# Peripheral.net
KiCad netlist of a schematic drawn in Altium Designer
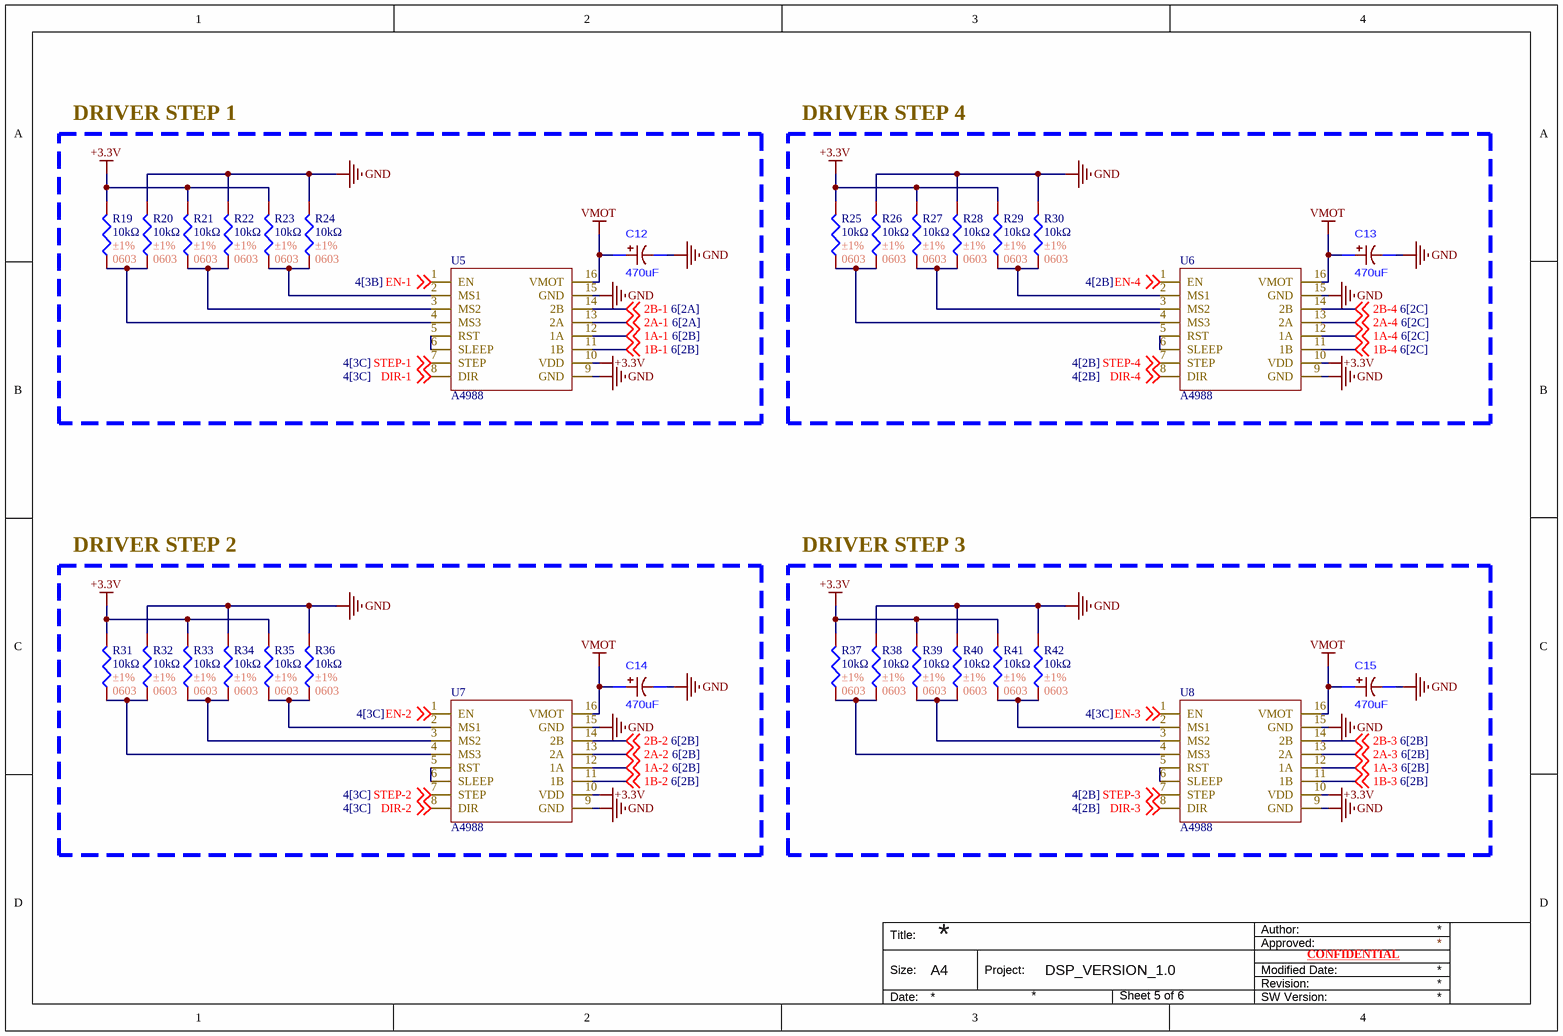
[diagram p0: Peripheral.SchDoc]

(export (version "E")
  (design (tool "Eeschema 10.0.6"))
  (components
    (comp (ref "C12")
      (value "470uF")
      (footprint "470uF 35V, D10xL13mm")
      (description "470uF ±20% 35V Through Hole,D10xL13mm")
      (fields (field (name "MANUFACTURER") "AISHI") (field (name "MFR. PART #") "SPZ1VM471G13O00RAXXX"))
      (libsource (lib "Capital") (part "470uF  35V, D10xL13mm"))
    )
    (comp (ref "C13")
      (value "470uF")
      (footprint "470uF 35V, D10xL13mm")
      (description "470uF ±20% 35V Through Hole,D10xL13mm")
      (fields (field (name "MANUFACTURER") "AISHI") (field (name "MFR. PART #") "SPZ1VM471G13O00RAXXX"))
      (libsource (lib "Capital") (part "470uF  35V, D10xL13mm"))
    )
    (comp (ref "C14")
      (value "470uF")
      (footprint "470uF 35V, D10xL13mm")
      (description "470uF ±20% 35V Through Hole,D10xL13mm")
      (fields (field (name "MANUFACTURER") "AISHI") (field (name "MFR. PART #") "SPZ1VM471G13O00RAXXX"))
      (libsource (lib "Capital") (part "470uF  35V, D10xL13mm"))
    )
    (comp (ref "C15")
      (value "470uF")
      (footprint "470uF 35V, D10xL13mm")
      (description "470uF ±20% 35V Through Hole,D10xL13mm")
      (fields (field (name "MANUFACTURER") "AISHI") (field (name "MFR. PART #") "SPZ1VM471G13O00RAXXX"))
      (libsource (lib "Capital") (part "470uF  35V, D10xL13mm"))
    )
    (comp (ref "R19")
      (value "10kΩ")
      (footprint "R0603")
      (description "62.5mW Thick Film Resistor 50V ±1% ±200ppm/℃ 10Ω 0402 Chip Resistor - Surface Mount ROHS")
      (fields
        (field (name "MANUFACTURER") "YAGEO")
        (field (name "MFR. PART #") "RC0402FR-0710RL")
        (field (name "TOLERANCE") "±1%")
        (field (name "PACKAGE") "0603")
      )
      (libsource (lib "Resistor") (part "R0603_10kΩ_±1%"))
    )
    (comp (ref "R20")
      (value "10kΩ")
      (footprint "R0603")
      (description "62.5mW Thick Film Resistor 50V ±1% ±200ppm/℃ 10Ω 0402 Chip Resistor - Surface Mount ROHS")
      (fields
        (field (name "MANUFACTURER") "YAGEO")
        (field (name "MFR. PART #") "RC0402FR-0710RL")
        (field (name "TOLERANCE") "±1%")
        (field (name "PACKAGE") "0603")
      )
      (libsource (lib "Resistor") (part "R0603_10kΩ_±1%"))
    )
    (comp (ref "R21")
      (value "10kΩ")
      (footprint "R0603")
      (description "62.5mW Thick Film Resistor 50V ±1% ±200ppm/℃ 10Ω 0402 Chip Resistor - Surface Mount ROHS")
      (fields
        (field (name "MANUFACTURER") "YAGEO")
        (field (name "MFR. PART #") "RC0402FR-0710RL")
        (field (name "TOLERANCE") "±1%")
        (field (name "PACKAGE") "0603")
      )
      (libsource (lib "Resistor") (part "R0603_10kΩ_±1%"))
    )
    (comp (ref "R22")
      (value "10kΩ")
      (footprint "R0603")
      (description "62.5mW Thick Film Resistor 50V ±1% ±200ppm/℃ 10Ω 0402 Chip Resistor - Surface Mount ROHS")
      (fields
        (field (name "MANUFACTURER") "YAGEO")
        (field (name "MFR. PART #") "RC0402FR-0710RL")
        (field (name "TOLERANCE") "±1%")
        (field (name "PACKAGE") "0603")
      )
      (libsource (lib "Resistor") (part "R0603_10kΩ_±1%"))
    )
    (comp (ref "R23")
      (value "10kΩ")
      (footprint "R0603")
      (description "62.5mW Thick Film Resistor 50V ±1% ±200ppm/℃ 10Ω 0402 Chip Resistor - Surface Mount ROHS")
      (fields
        (field (name "MANUFACTURER") "YAGEO")
        (field (name "MFR. PART #") "RC0402FR-0710RL")
        (field (name "TOLERANCE") "±1%")
        (field (name "PACKAGE") "0603")
      )
      (libsource (lib "Resistor") (part "R0603_10kΩ_±1%"))
    )
    (comp (ref "R24")
      (value "10kΩ")
      (footprint "R0603")
      (description "62.5mW Thick Film Resistor 50V ±1% ±200ppm/℃ 10Ω 0402 Chip Resistor - Surface Mount ROHS")
      (fields
        (field (name "MANUFACTURER") "YAGEO")
        (field (name "MFR. PART #") "RC0402FR-0710RL")
        (field (name "TOLERANCE") "±1%")
        (field (name "PACKAGE") "0603")
      )
      (libsource (lib "Resistor") (part "R0603_10kΩ_±1%"))
    )
    (comp (ref "R25")
      (value "10kΩ")
      (footprint "R0603")
      (description "62.5mW Thick Film Resistor 50V ±1% ±200ppm/℃ 10Ω 0402 Chip Resistor - Surface Mount ROHS")
      (fields
        (field (name "MANUFACTURER") "YAGEO")
        (field (name "MFR. PART #") "RC0402FR-0710RL")
        (field (name "TOLERANCE") "±1%")
        (field (name "PACKAGE") "0603")
      )
      (libsource (lib "Resistor") (part "R0603_10kΩ_±1%"))
    )
    (comp (ref "R26")
      (value "10kΩ")
      (footprint "R0603")
      (description "62.5mW Thick Film Resistor 50V ±1% ±200ppm/℃ 10Ω 0402 Chip Resistor - Surface Mount ROHS")
      (fields
        (field (name "MANUFACTURER") "YAGEO")
        (field (name "MFR. PART #") "RC0402FR-0710RL")
        (field (name "TOLERANCE") "±1%")
        (field (name "PACKAGE") "0603")
      )
      (libsource (lib "Resistor") (part "R0603_10kΩ_±1%"))
    )
    (comp (ref "R27")
      (value "10kΩ")
      (footprint "R0603")
      (description "62.5mW Thick Film Resistor 50V ±1% ±200ppm/℃ 10Ω 0402 Chip Resistor - Surface Mount ROHS")
      (fields
        (field (name "MANUFACTURER") "YAGEO")
        (field (name "MFR. PART #") "RC0402FR-0710RL")
        (field (name "TOLERANCE") "±1%")
        (field (name "PACKAGE") "0603")
      )
      (libsource (lib "Resistor") (part "R0603_10kΩ_±1%"))
    )
    (comp (ref "R28")
      (value "10kΩ")
      (footprint "R0603")
      (description "62.5mW Thick Film Resistor 50V ±1% ±200ppm/℃ 10Ω 0402 Chip Resistor - Surface Mount ROHS")
      (fields
        (field (name "MANUFACTURER") "YAGEO")
        (field (name "MFR. PART #") "RC0402FR-0710RL")
        (field (name "TOLERANCE") "±1%")
        (field (name "PACKAGE") "0603")
      )
      (libsource (lib "Resistor") (part "R0603_10kΩ_±1%"))
    )
    (comp (ref "R29")
      (value "10kΩ")
      (footprint "R0603")
      (description "62.5mW Thick Film Resistor 50V ±1% ±200ppm/℃ 10Ω 0402 Chip Resistor - Surface Mount ROHS")
      (fields
        (field (name "MANUFACTURER") "YAGEO")
        (field (name "MFR. PART #") "RC0402FR-0710RL")
        (field (name "TOLERANCE") "±1%")
        (field (name "PACKAGE") "0603")
      )
      (libsource (lib "Resistor") (part "R0603_10kΩ_±1%"))
    )
    (comp (ref "R30")
      (value "10kΩ")
      (footprint "R0603")
      (description "62.5mW Thick Film Resistor 50V ±1% ±200ppm/℃ 10Ω 0402 Chip Resistor - Surface Mount ROHS")
      (fields
        (field (name "MANUFACTURER") "YAGEO")
        (field (name "MFR. PART #") "RC0402FR-0710RL")
        (field (name "TOLERANCE") "±1%")
        (field (name "PACKAGE") "0603")
      )
      (libsource (lib "Resistor") (part "R0603_10kΩ_±1%"))
    )
    (comp (ref "R31")
      (value "10kΩ")
      (footprint "R0603")
      (description "62.5mW Thick Film Resistor 50V ±1% ±200ppm/℃ 10Ω 0402 Chip Resistor - Surface Mount ROHS")
      (fields
        (field (name "MANUFACTURER") "YAGEO")
        (field (name "MFR. PART #") "RC0402FR-0710RL")
        (field (name "TOLERANCE") "±1%")
        (field (name "PACKAGE") "0603")
      )
      (libsource (lib "Resistor") (part "R0603_10kΩ_±1%"))
    )
    (comp (ref "R32")
      (value "10kΩ")
      (footprint "R0603")
      (description "62.5mW Thick Film Resistor 50V ±1% ±200ppm/℃ 10Ω 0402 Chip Resistor - Surface Mount ROHS")
      (fields
        (field (name "MANUFACTURER") "YAGEO")
        (field (name "MFR. PART #") "RC0402FR-0710RL")
        (field (name "TOLERANCE") "±1%")
        (field (name "PACKAGE") "0603")
      )
      (libsource (lib "Resistor") (part "R0603_10kΩ_±1%"))
    )
    (comp (ref "R33")
      (value "10kΩ")
      (footprint "R0603")
      (description "62.5mW Thick Film Resistor 50V ±1% ±200ppm/℃ 10Ω 0402 Chip Resistor - Surface Mount ROHS")
      (fields
        (field (name "MANUFACTURER") "YAGEO")
        (field (name "MFR. PART #") "RC0402FR-0710RL")
        (field (name "TOLERANCE") "±1%")
        (field (name "PACKAGE") "0603")
      )
      (libsource (lib "Resistor") (part "R0603_10kΩ_±1%"))
    )
    (comp (ref "R34")
      (value "10kΩ")
      (footprint "R0603")
      (description "62.5mW Thick Film Resistor 50V ±1% ±200ppm/℃ 10Ω 0402 Chip Resistor - Surface Mount ROHS")
      (fields
        (field (name "MANUFACTURER") "YAGEO")
        (field (name "MFR. PART #") "RC0402FR-0710RL")
        (field (name "TOLERANCE") "±1%")
        (field (name "PACKAGE") "0603")
      )
      (libsource (lib "Resistor") (part "R0603_10kΩ_±1%"))
    )
    (comp (ref "R35")
      (value "10kΩ")
      (footprint "R0603")
      (description "62.5mW Thick Film Resistor 50V ±1% ±200ppm/℃ 10Ω 0402 Chip Resistor - Surface Mount ROHS")
      (fields
        (field (name "MANUFACTURER") "YAGEO")
        (field (name "MFR. PART #") "RC0402FR-0710RL")
        (field (name "TOLERANCE") "±1%")
        (field (name "PACKAGE") "0603")
      )
      (libsource (lib "Resistor") (part "R0603_10kΩ_±1%"))
    )
    (comp (ref "R36")
      (value "10kΩ")
      (footprint "R0603")
      (description "62.5mW Thick Film Resistor 50V ±1% ±200ppm/℃ 10Ω 0402 Chip Resistor - Surface Mount ROHS")
      (fields
        (field (name "MANUFACTURER") "YAGEO")
        (field (name "MFR. PART #") "RC0402FR-0710RL")
        (field (name "TOLERANCE") "±1%")
        (field (name "PACKAGE") "0603")
      )
      (libsource (lib "Resistor") (part "R0603_10kΩ_±1%"))
    )
    (comp (ref "R37")
      (value "10kΩ")
      (footprint "R0603")
      (description "62.5mW Thick Film Resistor 50V ±1% ±200ppm/℃ 10Ω 0402 Chip Resistor - Surface Mount ROHS")
      (fields
        (field (name "MANUFACTURER") "YAGEO")
        (field (name "MFR. PART #") "RC0402FR-0710RL")
        (field (name "TOLERANCE") "±1%")
        (field (name "PACKAGE") "0603")
      )
      (libsource (lib "Resistor") (part "R0603_10kΩ_±1%"))
    )
    (comp (ref "R38")
      (value "10kΩ")
      (footprint "R0603")
      (description "62.5mW Thick Film Resistor 50V ±1% ±200ppm/℃ 10Ω 0402 Chip Resistor - Surface Mount ROHS")
      (fields
        (field (name "MANUFACTURER") "YAGEO")
        (field (name "MFR. PART #") "RC0402FR-0710RL")
        (field (name "TOLERANCE") "±1%")
        (field (name "PACKAGE") "0603")
      )
      (libsource (lib "Resistor") (part "R0603_10kΩ_±1%"))
    )
    (comp (ref "R39")
      (value "10kΩ")
      (footprint "R0603")
      (description "62.5mW Thick Film Resistor 50V ±1% ±200ppm/℃ 10Ω 0402 Chip Resistor - Surface Mount ROHS")
      (fields
        (field (name "MANUFACTURER") "YAGEO")
        (field (name "MFR. PART #") "RC0402FR-0710RL")
        (field (name "TOLERANCE") "±1%")
        (field (name "PACKAGE") "0603")
      )
      (libsource (lib "Resistor") (part "R0603_10kΩ_±1%"))
    )
    (comp (ref "R40")
      (value "10kΩ")
      (footprint "R0603")
      (description "62.5mW Thick Film Resistor 50V ±1% ±200ppm/℃ 10Ω 0402 Chip Resistor - Surface Mount ROHS")
      (fields
        (field (name "MANUFACTURER") "YAGEO")
        (field (name "MFR. PART #") "RC0402FR-0710RL")
        (field (name "TOLERANCE") "±1%")
        (field (name "PACKAGE") "0603")
      )
      (libsource (lib "Resistor") (part "R0603_10kΩ_±1%"))
    )
    (comp (ref "R41")
      (value "10kΩ")
      (footprint "R0603")
      (description "62.5mW Thick Film Resistor 50V ±1% ±200ppm/℃ 10Ω 0402 Chip Resistor - Surface Mount ROHS")
      (fields
        (field (name "MANUFACTURER") "YAGEO")
        (field (name "MFR. PART #") "RC0402FR-0710RL")
        (field (name "TOLERANCE") "±1%")
        (field (name "PACKAGE") "0603")
      )
      (libsource (lib "Resistor") (part "R0603_10kΩ_±1%"))
    )
    (comp (ref "R42")
      (value "10kΩ")
      (footprint "R0603")
      (description "62.5mW Thick Film Resistor 50V ±1% ±200ppm/℃ 10Ω 0402 Chip Resistor - Surface Mount ROHS")
      (fields
        (field (name "MANUFACTURER") "YAGEO")
        (field (name "MFR. PART #") "RC0402FR-0710RL")
        (field (name "TOLERANCE") "±1%")
        (field (name "PACKAGE") "0603")
      )
      (libsource (lib "Resistor") (part "R0603_10kΩ_±1%"))
    )
    (comp (ref "U5")
      (value "A4988")
      (footprint "A4988-driver_step")
      (libsource (lib "IC") (part "Module_A4988"))
    )
    (comp (ref "U6")
      (value "A4988")
      (footprint "A4988-driver_step")
      (libsource (lib "IC") (part "Module_A4988"))
    )
    (comp (ref "U7")
      (value "A4988")
      (footprint "A4988-driver_step")
      (libsource (lib "IC") (part "Module_A4988"))
    )
    (comp (ref "U8")
      (value "A4988")
      (footprint "A4988-driver_step")
      (libsource (lib "IC") (part "Module_A4988"))
    )
  )
  (nets
    (net (code "1") (name "+3.3V") (class "Default")
      (node (ref "R19") (pin "2") (pinfunction "2_2") (pintype "passive"))
      (node (ref "R21") (pin "2") (pinfunction "2_2") (pintype "passive"))
      (node (ref "R23") (pin "2") (pinfunction "2_2") (pintype "passive"))
      (node (ref "R25") (pin "2") (pinfunction "2_2") (pintype "passive"))
      (node (ref "R27") (pin "2") (pinfunction "2_2") (pintype "passive"))
      (node (ref "R29") (pin "2") (pinfunction "2_2") (pintype "passive"))
      (node (ref "R31") (pin "2") (pinfunction "2_2") (pintype "passive"))
      (node (ref "R33") (pin "2") (pinfunction "2_2") (pintype "passive"))
      (node (ref "R35") (pin "2") (pinfunction "2_2") (pintype "passive"))
      (node (ref "R37") (pin "2") (pinfunction "2_2") (pintype "passive"))
      (node (ref "R39") (pin "2") (pinfunction "2_2") (pintype "passive"))
      (node (ref "R41") (pin "2") (pinfunction "2_2") (pintype "passive"))
      (node (ref "U5") (pin "10") (pinfunction "VDD_10") (pintype "passive"))
      (node (ref "U6") (pin "10") (pinfunction "VDD_10") (pintype "passive"))
      (node (ref "U7") (pin "10") (pinfunction "VDD_10") (pintype "passive"))
      (node (ref "U8") (pin "10") (pinfunction "VDD_10") (pintype "passive"))
    )
    (net (code "2") (name "1A-1") (class "Default")
      (node (ref "U5") (pin "12") (pinfunction "1A_12") (pintype "passive"))
    )
    (net (code "3") (name "1A-2") (class "Default")
      (node (ref "U7") (pin "12") (pinfunction "1A_12") (pintype "passive"))
    )
    (net (code "4") (name "1A-3") (class "Default")
      (node (ref "U8") (pin "12") (pinfunction "1A_12") (pintype "passive"))
    )
    (net (code "5") (name "1A-4") (class "Default")
      (node (ref "U6") (pin "12") (pinfunction "1A_12") (pintype "passive"))
    )
    (net (code "6") (name "1B-1") (class "Default")
      (node (ref "U5") (pin "11") (pinfunction "1B_11") (pintype "passive"))
    )
    (net (code "7") (name "1B-2") (class "Default")
      (node (ref "U7") (pin "11") (pinfunction "1B_11") (pintype "passive"))
    )
    (net (code "8") (name "1B-3") (class "Default")
      (node (ref "U8") (pin "11") (pinfunction "1B_11") (pintype "passive"))
    )
    (net (code "9") (name "1B-4") (class "Default")
      (node (ref "U6") (pin "11") (pinfunction "1B_11") (pintype "passive"))
    )
    (net (code "10") (name "2A-1") (class "Default")
      (node (ref "U5") (pin "13") (pinfunction "2A_13") (pintype "passive"))
    )
    (net (code "11") (name "2A-2") (class "Default")
      (node (ref "U7") (pin "13") (pinfunction "2A_13") (pintype "passive"))
    )
    (net (code "12") (name "2A-3") (class "Default")
      (node (ref "U8") (pin "13") (pinfunction "2A_13") (pintype "passive"))
    )
    (net (code "13") (name "2A-4") (class "Default")
      (node (ref "U6") (pin "13") (pinfunction "2A_13") (pintype "passive"))
    )
    (net (code "14") (name "2B-1") (class "Default")
      (node (ref "U5") (pin "14") (pinfunction "2B_14") (pintype "passive"))
    )
    (net (code "15") (name "2B-2") (class "Default")
      (node (ref "U7") (pin "14") (pinfunction "2B_14") (pintype "passive"))
    )
    (net (code "16") (name "2B-3") (class "Default")
      (node (ref "U8") (pin "14") (pinfunction "2B_14") (pintype "passive"))
    )
    (net (code "17") (name "2B-4") (class "Default")
      (node (ref "U6") (pin "14") (pinfunction "2B_14") (pintype "passive"))
    )
    (net (code "18") (name "DIR-1") (class "Default")
      (node (ref "U5") (pin "8") (pinfunction "DIR_8") (pintype "passive"))
    )
    (net (code "19") (name "DIR-2") (class "Default")
      (node (ref "U7") (pin "8") (pinfunction "DIR_8") (pintype "passive"))
    )
    (net (code "20") (name "DIR-3") (class "Default")
      (node (ref "U8") (pin "8") (pinfunction "DIR_8") (pintype "passive"))
    )
    (net (code "21") (name "DIR-4") (class "Default")
      (node (ref "U6") (pin "8") (pinfunction "DIR_8") (pintype "passive"))
    )
    (net (code "22") (name "EN-1") (class "Default")
      (node (ref "U5") (pin "1") (pinfunction "EN_1") (pintype "passive"))
    )
    (net (code "23") (name "EN-2") (class "Default")
      (node (ref "U7") (pin "1") (pinfunction "EN_1") (pintype "passive"))
    )
    (net (code "24") (name "EN-3") (class "Default")
      (node (ref "U8") (pin "1") (pinfunction "EN_1") (pintype "passive"))
    )
    (net (code "25") (name "EN-4") (class "Default")
      (node (ref "U6") (pin "1") (pinfunction "EN_1") (pintype "passive"))
    )
    (net (code "26") (name "GND") (class "Default")
      (node (ref "C12") (pin "2") (pinfunction "2_2") (pintype "passive"))
      (node (ref "C13") (pin "2") (pinfunction "2_2") (pintype "passive"))
      (node (ref "C14") (pin "2") (pinfunction "2_2") (pintype "passive"))
      (node (ref "C15") (pin "2") (pinfunction "2_2") (pintype "passive"))
      (node (ref "R20") (pin "2") (pinfunction "2_2") (pintype "passive"))
      (node (ref "R22") (pin "2") (pinfunction "2_2") (pintype "passive"))
      (node (ref "R24") (pin "2") (pinfunction "2_2") (pintype "passive"))
      (node (ref "R26") (pin "2") (pinfunction "2_2") (pintype "passive"))
      (node (ref "R28") (pin "2") (pinfunction "2_2") (pintype "passive"))
      (node (ref "R30") (pin "2") (pinfunction "2_2") (pintype "passive"))
      (node (ref "R32") (pin "2") (pinfunction "2_2") (pintype "passive"))
      (node (ref "R34") (pin "2") (pinfunction "2_2") (pintype "passive"))
      (node (ref "R36") (pin "2") (pinfunction "2_2") (pintype "passive"))
      (node (ref "R38") (pin "2") (pinfunction "2_2") (pintype "passive"))
      (node (ref "R40") (pin "2") (pinfunction "2_2") (pintype "passive"))
      (node (ref "R42") (pin "2") (pinfunction "2_2") (pintype "passive"))
      (node (ref "U5") (pin "15") (pinfunction "GND_15") (pintype "passive"))
      (node (ref "U5") (pin "9") (pinfunction "GND_9") (pintype "passive"))
      (node (ref "U6") (pin "15") (pinfunction "GND_15") (pintype "passive"))
      (node (ref "U6") (pin "9") (pinfunction "GND_9") (pintype "passive"))
      (node (ref "U7") (pin "15") (pinfunction "GND_15") (pintype "passive"))
      (node (ref "U7") (pin "9") (pinfunction "GND_9") (pintype "passive"))
      (node (ref "U8") (pin "15") (pinfunction "GND_15") (pintype "passive"))
      (node (ref "U8") (pin "9") (pinfunction "GND_9") (pintype "passive"))
    )
    (net (code "27") (name "Net-(U5-MS1)") (class "Default")
      (node (ref "R23") (pin "1") (pinfunction "1_1") (pintype "passive"))
      (node (ref "R24") (pin "1") (pinfunction "1_1") (pintype "passive"))
      (node (ref "U5") (pin "2") (pinfunction "MS1_2") (pintype "passive"))
    )
    (net (code "28") (name "Net-(U5-MS2)") (class "Default")
      (node (ref "R21") (pin "1") (pinfunction "1_1") (pintype "passive"))
      (node (ref "R22") (pin "1") (pinfunction "1_1") (pintype "passive"))
      (node (ref "U5") (pin "3") (pinfunction "MS2_3") (pintype "passive"))
    )
    (net (code "29") (name "Net-(U5-MS3)") (class "Default")
      (node (ref "R19") (pin "1") (pinfunction "1_1") (pintype "passive"))
      (node (ref "R20") (pin "1") (pinfunction "1_1") (pintype "passive"))
      (node (ref "U5") (pin "4") (pinfunction "MS3_4") (pintype "passive"))
    )
    (net (code "30") (name "Net-(U5-RST)") (class "Default")
      (node (ref "U5") (pin "5") (pinfunction "RST_5") (pintype "passive"))
      (node (ref "U5") (pin "6") (pinfunction "SLEEP_6") (pintype "passive"))
    )
    (net (code "31") (name "Net-(U6-MS1)") (class "Default")
      (node (ref "R29") (pin "1") (pinfunction "1_1") (pintype "passive"))
      (node (ref "R30") (pin "1") (pinfunction "1_1") (pintype "passive"))
      (node (ref "U6") (pin "2") (pinfunction "MS1_2") (pintype "passive"))
    )
    (net (code "32") (name "Net-(U6-MS2)") (class "Default")
      (node (ref "R27") (pin "1") (pinfunction "1_1") (pintype "passive"))
      (node (ref "R28") (pin "1") (pinfunction "1_1") (pintype "passive"))
      (node (ref "U6") (pin "3") (pinfunction "MS2_3") (pintype "passive"))
    )
    (net (code "33") (name "Net-(U6-MS3)") (class "Default")
      (node (ref "R25") (pin "1") (pinfunction "1_1") (pintype "passive"))
      (node (ref "R26") (pin "1") (pinfunction "1_1") (pintype "passive"))
      (node (ref "U6") (pin "4") (pinfunction "MS3_4") (pintype "passive"))
    )
    (net (code "34") (name "Net-(U6-RST)") (class "Default")
      (node (ref "U6") (pin "5") (pinfunction "RST_5") (pintype "passive"))
      (node (ref "U6") (pin "6") (pinfunction "SLEEP_6") (pintype "passive"))
    )
    (net (code "35") (name "Net-(U7-MS1)") (class "Default")
      (node (ref "R35") (pin "1") (pinfunction "1_1") (pintype "passive"))
      (node (ref "R36") (pin "1") (pinfunction "1_1") (pintype "passive"))
      (node (ref "U7") (pin "2") (pinfunction "MS1_2") (pintype "passive"))
    )
    (net (code "36") (name "Net-(U7-MS2)") (class "Default")
      (node (ref "R33") (pin "1") (pinfunction "1_1") (pintype "passive"))
      (node (ref "R34") (pin "1") (pinfunction "1_1") (pintype "passive"))
      (node (ref "U7") (pin "3") (pinfunction "MS2_3") (pintype "passive"))
    )
    (net (code "37") (name "Net-(U7-MS3)") (class "Default")
      (node (ref "R31") (pin "1") (pinfunction "1_1") (pintype "passive"))
      (node (ref "R32") (pin "1") (pinfunction "1_1") (pintype "passive"))
      (node (ref "U7") (pin "4") (pinfunction "MS3_4") (pintype "passive"))
    )
    (net (code "38") (name "Net-(U7-RST)") (class "Default")
      (node (ref "U7") (pin "5") (pinfunction "RST_5") (pintype "passive"))
      (node (ref "U7") (pin "6") (pinfunction "SLEEP_6") (pintype "passive"))
    )
    (net (code "39") (name "Net-(U8-MS1)") (class "Default")
      (node (ref "R41") (pin "1") (pinfunction "1_1") (pintype "passive"))
      (node (ref "R42") (pin "1") (pinfunction "1_1") (pintype "passive"))
      (node (ref "U8") (pin "2") (pinfunction "MS1_2") (pintype "passive"))
    )
    (net (code "40") (name "Net-(U8-MS2)") (class "Default")
      (node (ref "R39") (pin "1") (pinfunction "1_1") (pintype "passive"))
      (node (ref "R40") (pin "1") (pinfunction "1_1") (pintype "passive"))
      (node (ref "U8") (pin "3") (pinfunction "MS2_3") (pintype "passive"))
    )
    (net (code "41") (name "Net-(U8-MS3)") (class "Default")
      (node (ref "R37") (pin "1") (pinfunction "1_1") (pintype "passive"))
      (node (ref "R38") (pin "1") (pinfunction "1_1") (pintype "passive"))
      (node (ref "U8") (pin "4") (pinfunction "MS3_4") (pintype "passive"))
    )
    (net (code "42") (name "Net-(U8-RST)") (class "Default")
      (node (ref "U8") (pin "5") (pinfunction "RST_5") (pintype "passive"))
      (node (ref "U8") (pin "6") (pinfunction "SLEEP_6") (pintype "passive"))
    )
    (net (code "43") (name "STEP-1") (class "Default")
      (node (ref "U5") (pin "7") (pinfunction "STEP_7") (pintype "passive"))
    )
    (net (code "44") (name "STEP-2") (class "Default")
      (node (ref "U7") (pin "7") (pinfunction "STEP_7") (pintype "passive"))
    )
    (net (code "45") (name "STEP-3") (class "Default")
      (node (ref "U8") (pin "7") (pinfunction "STEP_7") (pintype "passive"))
    )
    (net (code "46") (name "STEP-4") (class "Default")
      (node (ref "U6") (pin "7") (pinfunction "STEP_7") (pintype "passive"))
    )
    (net (code "47") (name "VMOT") (class "Default")
      (node (ref "C12") (pin "1") (pinfunction "1_1") (pintype "passive"))
      (node (ref "C13") (pin "1") (pinfunction "1_1") (pintype "passive"))
      (node (ref "C14") (pin "1") (pinfunction "1_1") (pintype "passive"))
      (node (ref "C15") (pin "1") (pinfunction "1_1") (pintype "passive"))
      (node (ref "U5") (pin "16") (pinfunction "VMOT_16") (pintype "passive"))
      (node (ref "U6") (pin "16") (pinfunction "VMOT_16") (pintype "passive"))
      (node (ref "U7") (pin "16") (pinfunction "VMOT_16") (pintype "passive"))
      (node (ref "U8") (pin "16") (pinfunction "VMOT_16") (pintype "passive"))
    )
  )
)
